# MAX96724_COUPON.net
KiCad netlist of a schematic drawn in Altium Designer
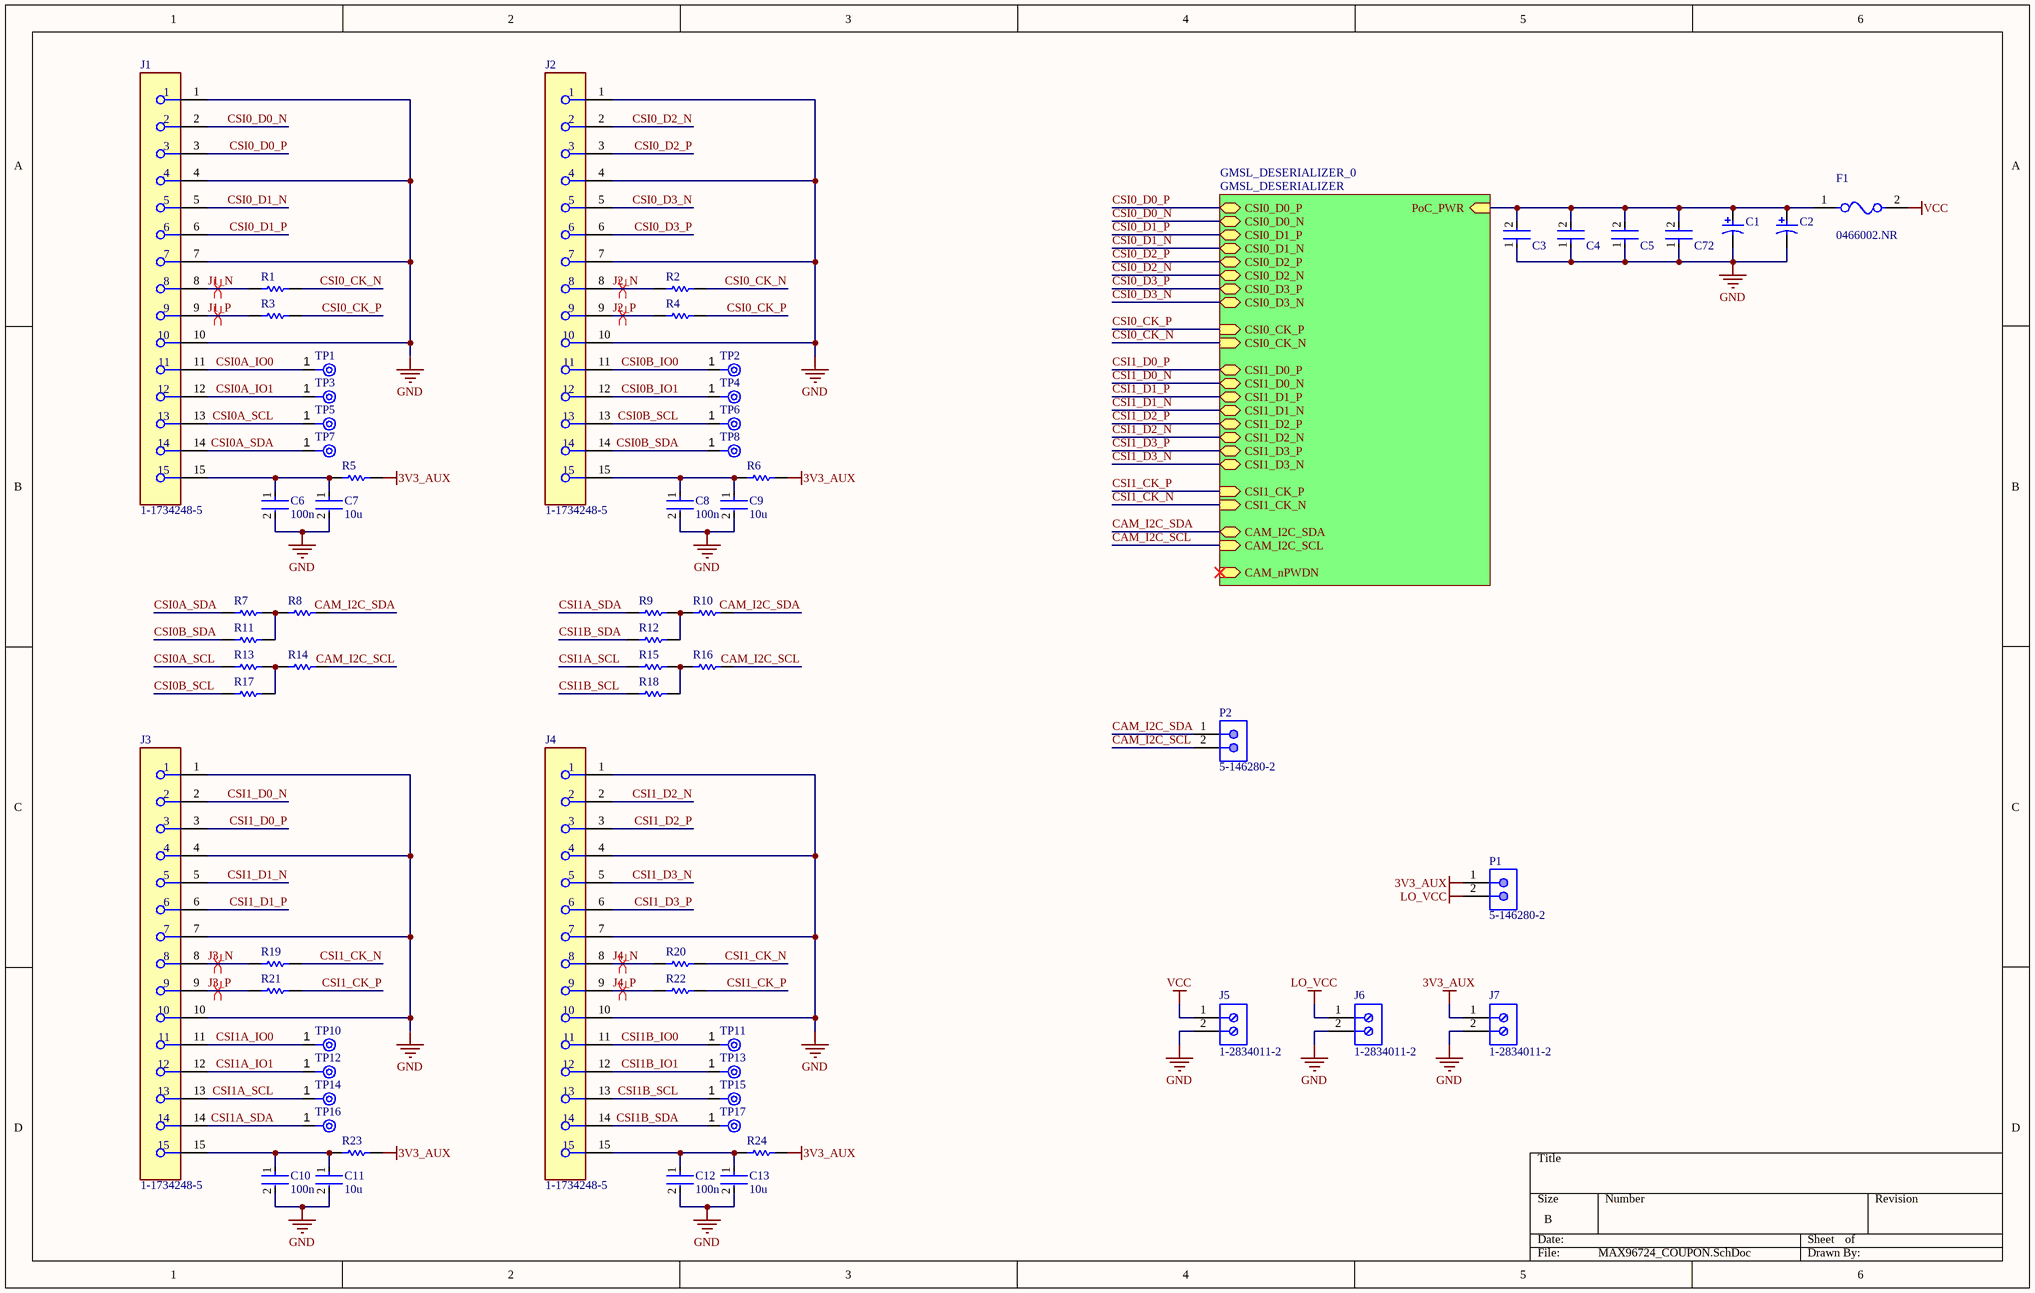
[diagram p0: MAX96724_COUPON.SchDoc]

(export (version "E")
  (design (tool "Eeschema 10.0.6"))
  (components
    (comp (ref "C1")
      (value "EEEFK1E101XP")
      (footprint "PNSC-FK-V-D8_V")
      (fields (field (name "MANUFACTURER") "Panasonic"))
      (libsource (lib "Altium Content Vault") (part "CAP-P-2"))
    )
    (comp (ref "C2")
      (value "EEEFK1E101XP")
      (footprint "PNSC-FK-V-D8_V")
      (fields (field (name "MANUFACTURER") "Panasonic"))
      (libsource (lib "Altium Content Vault") (part "CAP-P-2"))
    )
    (comp (ref "C3")
      (value "GRM21BR61E226ME44L")
      (footprint "FP-GRM21B-0_2-e0_2_0_7-IPC_B")
      (description "Chip Multilayer Ceramic Capacitors for General Purpose, 0805, 22uF, X5R, 15%, 20%, 25V")
      (fields (field (name "TOLERANCE") "20%") (field (name "VOLTAGE") "25V"))
      (libsource (lib "Altium Content Vault") (part "b4654b650e69147ec39a6b967a45e02"))
    )
    (comp (ref "C4")
      (value "GRM21BR61E226ME44L")
      (footprint "FP-GRM21B-0_2-e0_2_0_7-IPC_B")
      (description "Chip Multilayer Ceramic Capacitors for General Purpose, 0805, 22uF, X5R, 15%, 20%, 25V")
      (fields (field (name "TOLERANCE") "20%") (field (name "VOLTAGE") "25V"))
      (libsource (lib "Altium Content Vault") (part "b4654b650e69147ec39a6b967a45e02"))
    )
    (comp (ref "C5")
      (value "GRM21BR61E226ME44L")
      (footprint "FP-GRM21B-0_2-e0_2_0_7-IPC_B")
      (description "Chip Multilayer Ceramic Capacitors for General Purpose, 0805, 22uF, X5R, 15%, 20%, 25V")
      (fields (field (name "TOLERANCE") "20%") (field (name "VOLTAGE") "25V"))
      (libsource (lib "Altium Content Vault") (part "b4654b650e69147ec39a6b967a45e02"))
    )
    (comp (ref "C6")
      (value "100n")
      (footprint "FP-0402-L_1_0_0_05-W_0_5-IPC_A")
      (description "LARGE PADS, 0402 CAP, CHANGE COMMENT TO MATCH REAL P/N")
      (libsource (lib "Space Concordia") (part "b4654b650e69147ec39a6b967a45e02"))
    )
    (comp (ref "C7")
      (value "10u")
      (footprint "FP-0402-L_1_0_0_05-W_0_5-IPC_A")
      (description "LARGE PADS, 0402 CAP, CHANGE COMMENT TO MATCH REAL P/N")
      (libsource (lib "Space Concordia") (part "b4654b650e69147ec39a6b967a45e02"))
    )
    (comp (ref "C8")
      (value "100n")
      (footprint "FP-0402-L_1_0_0_05-W_0_5-IPC_A")
      (description "LARGE PADS, 0402 CAP, CHANGE COMMENT TO MATCH REAL P/N")
      (libsource (lib "Space Concordia") (part "b4654b650e69147ec39a6b967a45e02"))
    )
    (comp (ref "C9")
      (value "10u")
      (footprint "FP-0402-L_1_0_0_05-W_0_5-IPC_A")
      (description "LARGE PADS, 0402 CAP, CHANGE COMMENT TO MATCH REAL P/N")
      (libsource (lib "Space Concordia") (part "b4654b650e69147ec39a6b967a45e02"))
    )
    (comp (ref "C10")
      (value "100n")
      (footprint "FP-0402-L_1_0_0_05-W_0_5-IPC_A")
      (description "LARGE PADS, 0402 CAP, CHANGE COMMENT TO MATCH REAL P/N")
      (libsource (lib "Space Concordia") (part "b4654b650e69147ec39a6b967a45e02"))
    )
    (comp (ref "C11")
      (value "10u")
      (footprint "FP-0402-L_1_0_0_05-W_0_5-IPC_A")
      (description "LARGE PADS, 0402 CAP, CHANGE COMMENT TO MATCH REAL P/N")
      (libsource (lib "Space Concordia") (part "b4654b650e69147ec39a6b967a45e02"))
    )
    (comp (ref "C12")
      (value "100n")
      (footprint "FP-0402-L_1_0_0_05-W_0_5-IPC_A")
      (description "LARGE PADS, 0402 CAP, CHANGE COMMENT TO MATCH REAL P/N")
      (libsource (lib "Space Concordia") (part "b4654b650e69147ec39a6b967a45e02"))
    )
    (comp (ref "C13")
      (value "10u")
      (footprint "FP-0402-L_1_0_0_05-W_0_5-IPC_A")
      (description "LARGE PADS, 0402 CAP, CHANGE COMMENT TO MATCH REAL P/N")
      (libsource (lib "Space Concordia") (part "b4654b650e69147ec39a6b967a45e02"))
    )
    (comp (ref "C72")
      (value "GRM21BR61E226ME44L")
      (footprint "FP-GRM21B-0_2-e0_2_0_7-IPC_B")
      (description "Chip Multilayer Ceramic Capacitors for General Purpose, 0805, 22uF, X5R, 15%, 20%, 25V")
      (fields (field (name "TOLERANCE") "20%") (field (name "VOLTAGE") "25V"))
      (libsource (lib "Altium Content Vault") (part "b4654b650e69147ec39a6b967a45e02"))
    )
    (comp (ref "F1")
      (value "0466002.NR")
      (footprint "FP-0466-MFG")
      (description "FUSE BOARD MNT 2A 63VAC/VDC 1206")
      (fields
        (field (name "OCTOPART") "https://octopart.com/0466002.nr-littelfuse-566006")
        (field (name "MANUFACTURER") "Littelfuse")
      )
      (libsource (lib "Altium Content Vault") (part "5bcf9b9f640e542cf0359d10258e979"))
    )
    (comp (ref "J1")
      (value "1-1734248-5")
      (footprint "FP-1-1734248-5-MFG")
      (description "CONN FPC VERT 15POS 1.00MM SMD")
      (fields
        (field (name "MANUFACTURER") "TE")
        (field (name "OCTOPART") "https://octopart.com/1-1734248-5-te+connectivity-40620898")
      )
      (libsource (lib "Altium Content Vault") (part "a0777be16b290adccad2a8f9338c195"))
    )
    (comp (ref "J2")
      (value "1-1734248-5")
      (footprint "FP-1-1734248-5-MFG")
      (description "CONN FPC VERT 15POS 1.00MM SMD")
      (fields
        (field (name "MANUFACTURER") "TE")
        (field (name "OCTOPART") "https://octopart.com/1-1734248-5-te+connectivity-40620898")
      )
      (libsource (lib "Altium Content Vault") (part "a0777be16b290adccad2a8f9338c195"))
    )
    (comp (ref "J3")
      (value "1-1734248-5")
      (footprint "FP-1-1734248-5-MFG")
      (description "CONN FPC VERT 15POS 1.00MM SMD")
      (fields
        (field (name "MANUFACTURER") "TE")
        (field (name "OCTOPART") "https://octopart.com/1-1734248-5-te+connectivity-40620898")
      )
      (libsource (lib "Altium Content Vault") (part "a0777be16b290adccad2a8f9338c195"))
    )
    (comp (ref "J4")
      (value "1-1734248-5")
      (footprint "FP-1-1734248-5-MFG")
      (description "CONN FPC VERT 15POS 1.00MM SMD")
      (fields
        (field (name "MANUFACTURER") "TE")
        (field (name "OCTOPART") "https://octopart.com/1-1734248-5-te+connectivity-40620898")
      )
      (libsource (lib "Altium Content Vault") (part "a0777be16b290adccad2a8f9338c195"))
    )
    (comp (ref "J5")
      (value "1-2834011-2")
      (footprint "1-2834011-2-Footprint-1")
      (description "Barrier Strip Terminal Block")
      (libsource (lib "Space Concordia") (part "1-2834011-2"))
    )
    (comp (ref "J6")
      (value "1-2834011-2")
      (footprint "1-2834011-2-Footprint-1")
      (description "Barrier Strip Terminal Block")
      (libsource (lib "Space Concordia") (part "1-2834011-2"))
    )
    (comp (ref "J7")
      (value "1-2834011-2")
      (footprint "1-2834011-2-Footprint-1")
      (description "Barrier Strip Terminal Block")
      (libsource (lib "Space Concordia") (part "1-2834011-2"))
    )
    (comp (ref "P1")
      (value "5-146280-2")
      (footprint "TECO-5-146280-2_V")
      (fields (field (name "MANUFACTURER") "TE Connectivity"))
      (libsource (lib "Altium Content Vault") (part "CN-1P-M-R2"))
    )
    (comp (ref "P2")
      (value "5-146280-2")
      (footprint "TECO-5-146280-2_V")
      (fields (field (name "MANUFACTURER") "TE Connectivity"))
      (libsource (lib "Altium Content Vault") (part "CN-1P-M-R2"))
    )
    (comp (ref "R1")
      (value "0402 JUMPER")
      (footprint "RESC1005X40X25ML05T05")
      (description "READ THE NAME")
      (libsource (lib "Space Concordia") (part "CMP-009-00206-2"))
    )
    (comp (ref "R2")
      (value "0402 JUMPER")
      (footprint "RESC1005X40X25ML05T05")
      (description "READ THE NAME")
      (libsource (lib "Space Concordia") (part "CMP-009-00206-2"))
    )
    (comp (ref "R3")
      (value "0402 JUMPER")
      (footprint "RESC1005X40X25ML05T05")
      (description "READ THE NAME")
      (libsource (lib "Space Concordia") (part "CMP-009-00206-2"))
    )
    (comp (ref "R4")
      (value "0402 JUMPER")
      (footprint "RESC1005X40X25ML05T05")
      (description "READ THE NAME")
      (libsource (lib "Space Concordia") (part "CMP-009-00206-2"))
    )
    (comp (ref "R5")
      (value "RC0402JR-070RL")
      (footprint "RESC1005X40X25NL05T10")
      (fields (field (name "MANUFACTURER") "Yageo / Phycomp"))
      (libsource (lib "Altium Content Vault") (part "RES"))
    )
    (comp (ref "R6")
      (value "RC0402JR-070RL")
      (footprint "RESC1005X40X25NL05T10")
      (fields (field (name "MANUFACTURER") "Yageo / Phycomp"))
      (libsource (lib "Altium Content Vault") (part "RES"))
    )
    (comp (ref "R7")
      (value "RC0402JR-070RL")
      (footprint "RESC1005X40X25NL05T10")
      (fields (field (name "MANUFACTURER") "Yageo / Phycomp"))
      (libsource (lib "Altium Content Vault") (part "RES"))
    )
    (comp (ref "R8")
      (value "RC0402JR-070RL")
      (footprint "RESC1005X40X25NL05T10")
      (fields (field (name "MANUFACTURER") "Yageo / Phycomp"))
      (libsource (lib "Altium Content Vault") (part "RES"))
    )
    (comp (ref "R9")
      (value "RC0402JR-070RL")
      (footprint "RESC1005X40X25NL05T10")
      (fields (field (name "MANUFACTURER") "Yageo / Phycomp"))
      (libsource (lib "Altium Content Vault") (part "RES"))
    )
    (comp (ref "R10")
      (value "RC0402JR-070RL")
      (footprint "RESC1005X40X25NL05T10")
      (fields (field (name "MANUFACTURER") "Yageo / Phycomp"))
      (libsource (lib "Altium Content Vault") (part "RES"))
    )
    (comp (ref "R11")
      (value "RC0402JR-070RL")
      (footprint "RESC1005X40X25NL05T10")
      (fields (field (name "MANUFACTURER") "Yageo / Phycomp"))
      (libsource (lib "Altium Content Vault") (part "RES"))
    )
    (comp (ref "R12")
      (value "RC0402JR-070RL")
      (footprint "RESC1005X40X25NL05T10")
      (fields (field (name "MANUFACTURER") "Yageo / Phycomp"))
      (libsource (lib "Altium Content Vault") (part "RES"))
    )
    (comp (ref "R13")
      (value "RC0402JR-070RL")
      (footprint "RESC1005X40X25NL05T10")
      (fields (field (name "MANUFACTURER") "Yageo / Phycomp"))
      (libsource (lib "Altium Content Vault") (part "RES"))
    )
    (comp (ref "R14")
      (value "RC0402JR-070RL")
      (footprint "RESC1005X40X25NL05T10")
      (fields (field (name "MANUFACTURER") "Yageo / Phycomp"))
      (libsource (lib "Altium Content Vault") (part "RES"))
    )
    (comp (ref "R15")
      (value "RC0402JR-070RL")
      (footprint "RESC1005X40X25NL05T10")
      (fields (field (name "MANUFACTURER") "Yageo / Phycomp"))
      (libsource (lib "Altium Content Vault") (part "RES"))
    )
    (comp (ref "R16")
      (value "RC0402JR-070RL")
      (footprint "RESC1005X40X25NL05T10")
      (fields (field (name "MANUFACTURER") "Yageo / Phycomp"))
      (libsource (lib "Altium Content Vault") (part "RES"))
    )
    (comp (ref "R17")
      (value "RC0402JR-070RL")
      (footprint "RESC1005X40X25NL05T10")
      (fields (field (name "MANUFACTURER") "Yageo / Phycomp"))
      (libsource (lib "Altium Content Vault") (part "RES"))
    )
    (comp (ref "R18")
      (value "RC0402JR-070RL")
      (footprint "RESC1005X40X25NL05T10")
      (fields (field (name "MANUFACTURER") "Yageo / Phycomp"))
      (libsource (lib "Altium Content Vault") (part "RES"))
    )
    (comp (ref "R19")
      (value "0402 JUMPER")
      (footprint "RESC1005X40X25ML05T05")
      (description "READ THE NAME")
      (libsource (lib "Space Concordia") (part "CMP-009-00206-2"))
    )
    (comp (ref "R20")
      (value "0402 JUMPER")
      (footprint "RESC1005X40X25ML05T05")
      (description "READ THE NAME")
      (libsource (lib "Space Concordia") (part "CMP-009-00206-2"))
    )
    (comp (ref "R21")
      (value "0402 JUMPER")
      (footprint "RESC1005X40X25ML05T05")
      (description "READ THE NAME")
      (libsource (lib "Space Concordia") (part "CMP-009-00206-2"))
    )
    (comp (ref "R22")
      (value "0402 JUMPER")
      (footprint "RESC1005X40X25ML05T05")
      (description "READ THE NAME")
      (libsource (lib "Space Concordia") (part "CMP-009-00206-2"))
    )
    (comp (ref "R23")
      (value "RC0402JR-070RL")
      (footprint "RESC1005X40X25NL05T10")
      (fields (field (name "MANUFACTURER") "Yageo / Phycomp"))
      (libsource (lib "Altium Content Vault") (part "RES"))
    )
    (comp (ref "R24")
      (value "RC0402JR-070RL")
      (footprint "RESC1005X40X25NL05T10")
      (fields (field (name "MANUFACTURER") "Yageo / Phycomp"))
      (libsource (lib "Altium Content Vault") (part "RES"))
    )
    (comp (ref "TP1")
      (value "TPAD6R")
      (footprint "New footprint 1")
      (description "Test Point .6mm")
      (libsource (lib "Space Concordia") (part "TP"))
    )
    (comp (ref "TP2")
      (value "TPAD6R")
      (footprint "New footprint 1")
      (description "Test Point .6mm")
      (libsource (lib "Space Concordia") (part "TP"))
    )
    (comp (ref "TP3")
      (value "TPAD6R")
      (footprint "New footprint 1")
      (description "Test Point .6mm")
      (libsource (lib "Space Concordia") (part "TP"))
    )
    (comp (ref "TP4")
      (value "TPAD6R")
      (footprint "New footprint 1")
      (description "Test Point .6mm")
      (libsource (lib "Space Concordia") (part "TP"))
    )
    (comp (ref "TP5")
      (value "TPAD6R")
      (footprint "New footprint 1")
      (description "Test Point .6mm")
      (libsource (lib "Space Concordia") (part "TP"))
    )
    (comp (ref "TP6")
      (value "TPAD6R")
      (footprint "New footprint 1")
      (description "Test Point .6mm")
      (libsource (lib "Space Concordia") (part "TP"))
    )
    (comp (ref "TP7")
      (value "TPAD6R")
      (footprint "New footprint 1")
      (description "Test Point .6mm")
      (libsource (lib "Space Concordia") (part "TP"))
    )
    (comp (ref "TP8")
      (value "TPAD6R")
      (footprint "New footprint 1")
      (description "Test Point .6mm")
      (libsource (lib "Space Concordia") (part "TP"))
    )
    (comp (ref "TP10")
      (value "TPAD6R")
      (footprint "New footprint 1")
      (description "Test Point .6mm")
      (libsource (lib "Space Concordia") (part "TP"))
    )
    (comp (ref "TP11")
      (value "TPAD6R")
      (footprint "New footprint 1")
      (description "Test Point .6mm")
      (libsource (lib "Space Concordia") (part "TP"))
    )
    (comp (ref "TP12")
      (value "TPAD6R")
      (footprint "New footprint 1")
      (description "Test Point .6mm")
      (libsource (lib "Space Concordia") (part "TP"))
    )
    (comp (ref "TP13")
      (value "TPAD6R")
      (footprint "New footprint 1")
      (description "Test Point .6mm")
      (libsource (lib "Space Concordia") (part "TP"))
    )
    (comp (ref "TP14")
      (value "TPAD6R")
      (footprint "New footprint 1")
      (description "Test Point .6mm")
      (libsource (lib "Space Concordia") (part "TP"))
    )
    (comp (ref "TP15")
      (value "TPAD6R")
      (footprint "New footprint 1")
      (description "Test Point .6mm")
      (libsource (lib "Space Concordia") (part "TP"))
    )
    (comp (ref "TP16")
      (value "TPAD6R")
      (footprint "New footprint 1")
      (description "Test Point .6mm")
      (libsource (lib "Space Concordia") (part "TP"))
    )
    (comp (ref "TP17")
      (value "TPAD6R")
      (footprint "New footprint 1")
      (description "Test Point .6mm")
      (libsource (lib "Space Concordia") (part "TP"))
    )
  )
  (nets
    (net (code "1") (name "/CAM_I2C_SCL") (class "Default")
      (node (ref "P2") (pin "2") (pinfunction "2_2") (pintype "passive"))
      (node (ref "R14") (pin "2") (pinfunction "2_2") (pintype "passive"))
      (node (ref "R16") (pin "2") (pinfunction "2_2") (pintype "passive"))
    )
    (net (code "2") (name "/CAM_I2C_SDA") (class "Default")
      (node (ref "P2") (pin "1") (pinfunction "1_1") (pintype "passive"))
      (node (ref "R10") (pin "2") (pinfunction "2_2") (pintype "passive"))
      (node (ref "R8") (pin "2") (pinfunction "2_2") (pintype "passive"))
    )
    (net (code "4") (name "/CSI0A_IO0") (class "Default")
      (node (ref "J1") (pin "11") (pinfunction "11_11") (pintype "passive"))
      (node (ref "TP1") (pin "1") (pinfunction "TP_1") (pintype "passive"))
    )
    (net (code "5") (name "/CSI0A_IO1") (class "Default")
      (node (ref "J1") (pin "12") (pinfunction "12_12") (pintype "passive"))
      (node (ref "TP3") (pin "1") (pinfunction "TP_1") (pintype "passive"))
    )
    (net (code "6") (name "/CSI0A_SCL") (class "Default")
      (node (ref "J1") (pin "13") (pinfunction "13_13") (pintype "passive"))
      (node (ref "R13") (pin "1") (pinfunction "1_1") (pintype "passive"))
      (node (ref "TP5") (pin "1") (pinfunction "TP_1") (pintype "passive"))
    )
    (net (code "7") (name "/CSI0A_SDA") (class "Default")
      (node (ref "J1") (pin "14") (pinfunction "14_14") (pintype "passive"))
      (node (ref "R7") (pin "1") (pinfunction "1_1") (pintype "passive"))
      (node (ref "TP7") (pin "1") (pinfunction "TP_1") (pintype "passive"))
    )
    (net (code "8") (name "/CSI0B_IO0") (class "Default")
      (node (ref "J2") (pin "11") (pinfunction "11_11") (pintype "passive"))
      (node (ref "TP2") (pin "1") (pinfunction "TP_1") (pintype "passive"))
    )
    (net (code "9") (name "/CSI0B_IO1") (class "Default")
      (node (ref "J2") (pin "12") (pinfunction "12_12") (pintype "passive"))
      (node (ref "TP4") (pin "1") (pinfunction "TP_1") (pintype "passive"))
    )
    (net (code "10") (name "/CSI0B_SCL") (class "Default")
      (node (ref "J2") (pin "13") (pinfunction "13_13") (pintype "passive"))
      (node (ref "R17") (pin "1") (pinfunction "1_1") (pintype "passive"))
      (node (ref "TP6") (pin "1") (pinfunction "TP_1") (pintype "passive"))
    )
    (net (code "11") (name "/CSI0B_SDA") (class "Default")
      (node (ref "J2") (pin "14") (pinfunction "14_14") (pintype "passive"))
      (node (ref "R11") (pin "1") (pinfunction "1_1") (pintype "passive"))
      (node (ref "TP8") (pin "1") (pinfunction "TP_1") (pintype "passive"))
    )
    (net (code "12") (name "/CSI0_CK_N") (class "Default")
      (node (ref "R1") (pin "2") (pinfunction "2_2") (pintype "passive"))
      (node (ref "R2") (pin "2") (pinfunction "2_2") (pintype "passive"))
    )
    (net (code "13") (name "/CSI0_CK_P") (class "Default")
      (node (ref "R3") (pin "2") (pinfunction "2_2") (pintype "passive"))
      (node (ref "R4") (pin "2") (pinfunction "2_2") (pintype "passive"))
    )
    (net (code "14") (name "/CSI0_D0_N") (class "Default")
      (node (ref "J1") (pin "2") (pinfunction "2_2") (pintype "passive"))
    )
    (net (code "15") (name "/CSI0_D0_P") (class "Default")
      (node (ref "J1") (pin "3") (pinfunction "3_3") (pintype "passive"))
    )
    (net (code "16") (name "/CSI0_D1_N") (class "Default")
      (node (ref "J1") (pin "5") (pinfunction "5_5") (pintype "passive"))
    )
    (net (code "17") (name "/CSI0_D1_P") (class "Default")
      (node (ref "J1") (pin "6") (pinfunction "6_6") (pintype "passive"))
    )
    (net (code "18") (name "/CSI0_D2_N") (class "Default")
      (node (ref "J2") (pin "2") (pinfunction "2_2") (pintype "passive"))
    )
    (net (code "19") (name "/CSI0_D2_P") (class "Default")
      (node (ref "J2") (pin "3") (pinfunction "3_3") (pintype "passive"))
    )
    (net (code "20") (name "/CSI0_D3_N") (class "Default")
      (node (ref "J2") (pin "5") (pinfunction "5_5") (pintype "passive"))
    )
    (net (code "21") (name "/CSI0_D3_P") (class "Default")
      (node (ref "J2") (pin "6") (pinfunction "6_6") (pintype "passive"))
    )
    (net (code "22") (name "/CSI1A_IO0") (class "Default")
      (node (ref "J3") (pin "11") (pinfunction "11_11") (pintype "passive"))
      (node (ref "TP10") (pin "1") (pinfunction "TP_1") (pintype "passive"))
    )
    (net (code "23") (name "/CSI1A_IO1") (class "Default")
      (node (ref "J3") (pin "12") (pinfunction "12_12") (pintype "passive"))
      (node (ref "TP12") (pin "1") (pinfunction "TP_1") (pintype "passive"))
    )
    (net (code "24") (name "/CSI1A_SCL") (class "Default")
      (node (ref "J3") (pin "13") (pinfunction "13_13") (pintype "passive"))
      (node (ref "R15") (pin "1") (pinfunction "1_1") (pintype "passive"))
      (node (ref "TP14") (pin "1") (pinfunction "TP_1") (pintype "passive"))
    )
    (net (code "25") (name "/CSI1A_SDA") (class "Default")
      (node (ref "J3") (pin "14") (pinfunction "14_14") (pintype "passive"))
      (node (ref "R9") (pin "1") (pinfunction "1_1") (pintype "passive"))
      (node (ref "TP16") (pin "1") (pinfunction "TP_1") (pintype "passive"))
    )
    (net (code "26") (name "/CSI1B_IO0") (class "Default")
      (node (ref "J4") (pin "11") (pinfunction "11_11") (pintype "passive"))
      (node (ref "TP11") (pin "1") (pinfunction "TP_1") (pintype "passive"))
    )
    (net (code "27") (name "/CSI1B_IO1") (class "Default")
      (node (ref "J4") (pin "12") (pinfunction "12_12") (pintype "passive"))
      (node (ref "TP13") (pin "1") (pinfunction "TP_1") (pintype "passive"))
    )
    (net (code "28") (name "/CSI1B_SCL") (class "Default")
      (node (ref "J4") (pin "13") (pinfunction "13_13") (pintype "passive"))
      (node (ref "R18") (pin "1") (pinfunction "1_1") (pintype "passive"))
      (node (ref "TP15") (pin "1") (pinfunction "TP_1") (pintype "passive"))
    )
    (net (code "29") (name "/CSI1B_SDA") (class "Default")
      (node (ref "J4") (pin "14") (pinfunction "14_14") (pintype "passive"))
      (node (ref "R12") (pin "1") (pinfunction "1_1") (pintype "passive"))
      (node (ref "TP17") (pin "1") (pinfunction "TP_1") (pintype "passive"))
    )
    (net (code "30") (name "/CSI1_CK_N") (class "Default")
      (node (ref "R19") (pin "2") (pinfunction "2_2") (pintype "passive"))
      (node (ref "R20") (pin "2") (pinfunction "2_2") (pintype "passive"))
    )
    (net (code "31") (name "/CSI1_CK_P") (class "Default")
      (node (ref "R21") (pin "2") (pinfunction "2_2") (pintype "passive"))
      (node (ref "R22") (pin "2") (pinfunction "2_2") (pintype "passive"))
    )
    (net (code "32") (name "/CSI1_D0_N") (class "Default")
      (node (ref "J3") (pin "2") (pinfunction "2_2") (pintype "passive"))
    )
    (net (code "33") (name "/CSI1_D0_P") (class "Default")
      (node (ref "J3") (pin "3") (pinfunction "3_3") (pintype "passive"))
    )
    (net (code "34") (name "/CSI1_D1_N") (class "Default")
      (node (ref "J3") (pin "5") (pinfunction "5_5") (pintype "passive"))
    )
    (net (code "35") (name "/CSI1_D1_P") (class "Default")
      (node (ref "J3") (pin "6") (pinfunction "6_6") (pintype "passive"))
    )
    (net (code "36") (name "/CSI1_D2_N") (class "Default")
      (node (ref "J4") (pin "2") (pinfunction "2_2") (pintype "passive"))
    )
    (net (code "37") (name "/CSI1_D2_P") (class "Default")
      (node (ref "J4") (pin "3") (pinfunction "3_3") (pintype "passive"))
    )
    (net (code "38") (name "/CSI1_D3_N") (class "Default")
      (node (ref "J4") (pin "5") (pinfunction "5_5") (pintype "passive"))
    )
    (net (code "39") (name "/CSI1_D3_P") (class "Default")
      (node (ref "J4") (pin "6") (pinfunction "6_6") (pintype "passive"))
    )
    (net (code "40") (name "/J1_N") (class "Default")
      (node (ref "J1") (pin "8") (pinfunction "8_8") (pintype "passive"))
      (node (ref "R1") (pin "1") (pinfunction "1_1") (pintype "passive"))
    )
    (net (code "41") (name "/J1_P") (class "Default")
      (node (ref "J1") (pin "9") (pinfunction "9_9") (pintype "passive"))
      (node (ref "R3") (pin "1") (pinfunction "1_1") (pintype "passive"))
    )
    (net (code "42") (name "/J2_N") (class "Default")
      (node (ref "J2") (pin "8") (pinfunction "8_8") (pintype "passive"))
      (node (ref "R2") (pin "1") (pinfunction "1_1") (pintype "passive"))
    )
    (net (code "43") (name "/J2_P") (class "Default")
      (node (ref "J2") (pin "9") (pinfunction "9_9") (pintype "passive"))
      (node (ref "R4") (pin "1") (pinfunction "1_1") (pintype "passive"))
    )
    (net (code "44") (name "/J3_N") (class "Default")
      (node (ref "J3") (pin "8") (pinfunction "8_8") (pintype "passive"))
      (node (ref "R19") (pin "1") (pinfunction "1_1") (pintype "passive"))
    )
    (net (code "45") (name "/J3_P") (class "Default")
      (node (ref "J3") (pin "9") (pinfunction "9_9") (pintype "passive"))
      (node (ref "R21") (pin "1") (pinfunction "1_1") (pintype "passive"))
    )
    (net (code "46") (name "/J4_N") (class "Default")
      (node (ref "J4") (pin "8") (pinfunction "8_8") (pintype "passive"))
      (node (ref "R20") (pin "1") (pinfunction "1_1") (pintype "passive"))
    )
    (net (code "47") (name "/J4_P") (class "Default")
      (node (ref "J4") (pin "9") (pinfunction "9_9") (pintype "passive"))
      (node (ref "R22") (pin "1") (pinfunction "1_1") (pintype "passive"))
    )
    (net (code "48") (name "/PoC_PWR") (class "Default")
      (node (ref "C1") (pin "1") (pinfunction "1_1") (pintype "passive"))
      (node (ref "C2") (pin "1") (pinfunction "1_1") (pintype "passive"))
      (node (ref "C3") (pin "2") (pinfunction "2_2") (pintype "passive"))
      (node (ref "C4") (pin "2") (pinfunction "2_2") (pintype "passive"))
      (node (ref "C5") (pin "2") (pinfunction "2_2") (pintype "passive"))
      (node (ref "C72") (pin "2") (pinfunction "2_2") (pintype "passive"))
      (node (ref "F1") (pin "1") (pinfunction "1_1") (pintype "passive"))
    )
    (net (code "49") (name "3V3_AUX") (class "Default")
      (node (ref "J7") (pin "1") (pinfunction "1_1") (pintype "passive"))
      (node (ref "P1") (pin "1") (pinfunction "1_1") (pintype "passive"))
      (node (ref "R23") (pin "2") (pinfunction "2_2") (pintype "passive"))
      (node (ref "R24") (pin "2") (pinfunction "2_2") (pintype "passive"))
      (node (ref "R5") (pin "2") (pinfunction "2_2") (pintype "passive"))
      (node (ref "R6") (pin "2") (pinfunction "2_2") (pintype "passive"))
    )
    (net (code "50") (name "GND") (class "Default")
      (node (ref "C1") (pin "2") (pinfunction "2_2") (pintype "passive"))
      (node (ref "C10") (pin "2") (pinfunction "2_2") (pintype "passive"))
      (node (ref "C11") (pin "2") (pinfunction "2_2") (pintype "passive"))
      (node (ref "C12") (pin "2") (pinfunction "2_2") (pintype "passive"))
      (node (ref "C13") (pin "2") (pinfunction "2_2") (pintype "passive"))
      (node (ref "C2") (pin "2") (pinfunction "2_2") (pintype "passive"))
      (node (ref "C3") (pin "1") (pinfunction "1_1") (pintype "passive"))
      (node (ref "C4") (pin "1") (pinfunction "1_1") (pintype "passive"))
      (node (ref "C5") (pin "1") (pinfunction "1_1") (pintype "passive"))
      (node (ref "C6") (pin "2") (pinfunction "2_2") (pintype "passive"))
      (node (ref "C7") (pin "2") (pinfunction "2_2") (pintype "passive"))
      (node (ref "C72") (pin "1") (pinfunction "1_1") (pintype "passive"))
      (node (ref "C8") (pin "2") (pinfunction "2_2") (pintype "passive"))
      (node (ref "C9") (pin "2") (pinfunction "2_2") (pintype "passive"))
      (node (ref "J1") (pin "1") (pinfunction "1_1") (pintype "passive"))
      (node (ref "J1") (pin "10") (pinfunction "10_10") (pintype "passive"))
      (node (ref "J1") (pin "4") (pinfunction "4_4") (pintype "passive"))
      (node (ref "J1") (pin "7") (pinfunction "7_7") (pintype "passive"))
      (node (ref "J2") (pin "1") (pinfunction "1_1") (pintype "passive"))
      (node (ref "J2") (pin "10") (pinfunction "10_10") (pintype "passive"))
      (node (ref "J2") (pin "4") (pinfunction "4_4") (pintype "passive"))
      (node (ref "J2") (pin "7") (pinfunction "7_7") (pintype "passive"))
      (node (ref "J3") (pin "1") (pinfunction "1_1") (pintype "passive"))
      (node (ref "J3") (pin "10") (pinfunction "10_10") (pintype "passive"))
      (node (ref "J3") (pin "4") (pinfunction "4_4") (pintype "passive"))
      (node (ref "J3") (pin "7") (pinfunction "7_7") (pintype "passive"))
      (node (ref "J4") (pin "1") (pinfunction "1_1") (pintype "passive"))
      (node (ref "J4") (pin "10") (pinfunction "10_10") (pintype "passive"))
      (node (ref "J4") (pin "4") (pinfunction "4_4") (pintype "passive"))
      (node (ref "J4") (pin "7") (pinfunction "7_7") (pintype "passive"))
      (node (ref "J5") (pin "2") (pinfunction "2_2") (pintype "passive"))
      (node (ref "J6") (pin "2") (pinfunction "2_2") (pintype "passive"))
      (node (ref "J7") (pin "2") (pinfunction "2_2") (pintype "passive"))
    )
    (net (code "51") (name "LO_VCC") (class "Default")
      (node (ref "J6") (pin "1") (pinfunction "1_1") (pintype "passive"))
      (node (ref "P1") (pin "2") (pinfunction "2_2") (pintype "passive"))
    )
    (net (code "52") (name "Net-(C6-Pad1)") (class "Default")
      (node (ref "C6") (pin "1") (pinfunction "1_1") (pintype "passive"))
      (node (ref "C7") (pin "1") (pinfunction "1_1") (pintype "passive"))
      (node (ref "J1") (pin "15") (pinfunction "15_15") (pintype "passive"))
      (node (ref "R5") (pin "1") (pinfunction "1_1") (pintype "passive"))
    )
    (net (code "53") (name "Net-(C8-Pad1)") (class "Default")
      (node (ref "C8") (pin "1") (pinfunction "1_1") (pintype "passive"))
      (node (ref "C9") (pin "1") (pinfunction "1_1") (pintype "passive"))
      (node (ref "J2") (pin "15") (pinfunction "15_15") (pintype "passive"))
      (node (ref "R6") (pin "1") (pinfunction "1_1") (pintype "passive"))
    )
    (net (code "54") (name "Net-(C10-Pad1)") (class "Default")
      (node (ref "C10") (pin "1") (pinfunction "1_1") (pintype "passive"))
      (node (ref "C11") (pin "1") (pinfunction "1_1") (pintype "passive"))
      (node (ref "J3") (pin "15") (pinfunction "15_15") (pintype "passive"))
      (node (ref "R23") (pin "1") (pinfunction "1_1") (pintype "passive"))
    )
    (net (code "55") (name "Net-(C12-Pad1)") (class "Default")
      (node (ref "C12") (pin "1") (pinfunction "1_1") (pintype "passive"))
      (node (ref "C13") (pin "1") (pinfunction "1_1") (pintype "passive"))
      (node (ref "J4") (pin "15") (pinfunction "15_15") (pintype "passive"))
      (node (ref "R24") (pin "1") (pinfunction "1_1") (pintype "passive"))
    )
    (net (code "56") (name "Net-(R10-Pad1)") (class "Default")
      (node (ref "R10") (pin "1") (pinfunction "1_1") (pintype "passive"))
      (node (ref "R12") (pin "2") (pinfunction "2_2") (pintype "passive"))
      (node (ref "R9") (pin "2") (pinfunction "2_2") (pintype "passive"))
    )
    (net (code "57") (name "Net-(R11-Pad2)") (class "Default")
      (node (ref "R11") (pin "2") (pinfunction "2_2") (pintype "passive"))
      (node (ref "R7") (pin "2") (pinfunction "2_2") (pintype "passive"))
      (node (ref "R8") (pin "1") (pinfunction "1_1") (pintype "passive"))
    )
    (net (code "58") (name "Net-(R13-Pad2)") (class "Default")
      (node (ref "R13") (pin "2") (pinfunction "2_2") (pintype "passive"))
      (node (ref "R14") (pin "1") (pinfunction "1_1") (pintype "passive"))
      (node (ref "R17") (pin "2") (pinfunction "2_2") (pintype "passive"))
    )
    (net (code "59") (name "Net-(R15-Pad2)") (class "Default")
      (node (ref "R15") (pin "2") (pinfunction "2_2") (pintype "passive"))
      (node (ref "R16") (pin "1") (pinfunction "1_1") (pintype "passive"))
      (node (ref "R18") (pin "2") (pinfunction "2_2") (pintype "passive"))
    )
    (net (code "60") (name "VCC") (class "Default")
      (node (ref "F1") (pin "2") (pinfunction "2_2") (pintype "passive"))
      (node (ref "J5") (pin "1") (pinfunction "1_1") (pintype "passive"))
    )
  )
)
